# DCDC_5V.net
KiCad netlist of a schematic drawn in Altium Designer
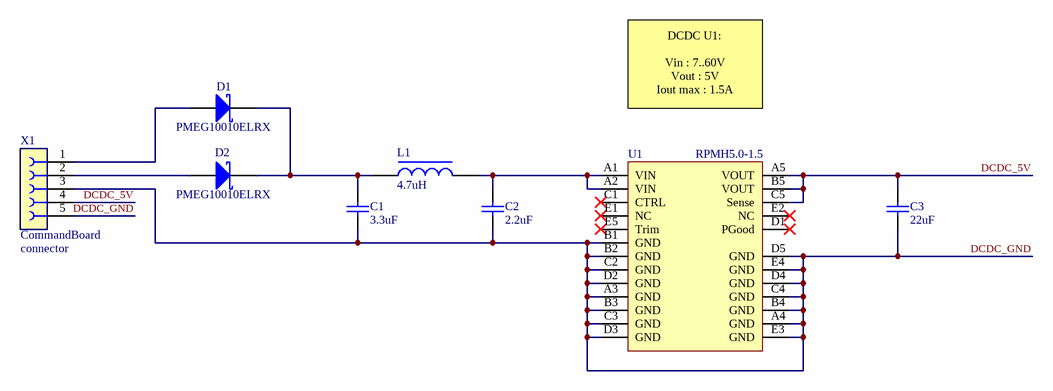
[diagram p0: DCDC_5V.SchDoc]

(export (version "E")
  (design (tool "Eeschema 10.0.6"))
  (components
    (comp (ref "C1")
      (value "3.3uF")
      (footprint "DCDC_5V:CAPC3216X19N")
      (description "3,3µF ±10% 100V Condensateurs céramique X7S 1206 (3216 métrique)")
      (fields (field (name "Comment") "CAP CER 3.3uF 1206"))
      (libsource (lib "DCDC_5V") (part "CAP CER 3.3uF 10% 100V 1206"))
    )
    (comp (ref "C2")
      (value "2.2uF")
      (footprint "DCDC_5V:CAPC3216X19N")
      (description "2,2µF ±10% 75V Condensateurs céramique X7R 1206 (3216 métrique)")
      (fields (field (name "Comment") "CAP CER 2.2uF 1206"))
      (libsource (lib "DCDC_5V") (part "CAP CER 2.2uF 10% 75V 1206"))
    )
    (comp (ref "C3")
      (value "22uF")
      (footprint "DCDC_5V:CAPC1608X08N")
      (description "22µF ±20% 6,3V Condensateurs céramique X5R 0603 (1608 métrique)")
      (fields (field (name "Comment") "CAP CER 22uF 0603"))
      (libsource (lib "DCDC_5V") (part "CAP CER 22uF 200% 6V3 0603"))
    )
    (comp (ref "D1")
      (value "PMEG10010ELRX")
      (footprint "DCDC_5V:DIOM2617X11N")
      (description "Diode Schottky 100V 1A Montage en surface CFP3")
      (fields (field (name "Comment") "DIODE SCHOTTKY 100V 1A SOD123"))
      (libsource (lib "DCDC_5V") (part "DIODE SCHOTTKY 100V 1A SOD123"))
    )
    (comp (ref "D2")
      (value "PMEG10010ELRX")
      (footprint "DCDC_5V:DIOM2617X11N")
      (description "Diode Schottky 100V 1A Montage en surface CFP3")
      (fields (field (name "Comment") "DIODE SCHOTTKY 100V 1A SOD123"))
      (libsource (lib "DCDC_5V") (part "DIODE SCHOTTKY 100V 1A SOD123"))
    )
    (comp (ref "L1")
      (value "4.7uH")
      (footprint "DCDC_5V:INDC2520X12N")
      (description "4,7µH Blindé Inducteur 1,5A 190mOhms maxi 1008 (2520 métrique)")
      (fields (field (name "Comment") "IND SMD 2020"))
      (libsource (lib "DCDC_5V") (part "IND SMD 4.7uH"))
    )
    (comp (ref "U1")
      (value "RPMH5.0-1.5")
      (footprint "DCDC_5V:CONV_RPMH5.0-1.5")
      (fields (field (name "Comment") "DCDC 5V 1.5A"))
      (libsource (lib "DCDC_5V") (part "RPMH5.0-1.5"))
    )
    (comp (ref "X1")
      (value "CONNECT HEADER 5pos 180°")
      (footprint "DCDC_5V:62000611821 - 5pin")
      (fields (field (name "USE") "CommandBoard") (field (name "SYSTEM") "connector"))
      (libsource (lib "DCDC_5V") (part "CONNECT HEADER 5pos 180° 2mm"))
    )
  )
  (nets
    (net (code "1") (name "/DCDC_5V") (class "Default")
      (node (ref "C3") (pin "2") (pinfunction "2_2") (pintype "passive"))
      (node (ref "U1") (pin "A5") (pinfunction "VOUT_A5") (pintype "power_in"))
      (node (ref "U1") (pin "B5") (pinfunction "VOUT_B5") (pintype "power_in"))
      (node (ref "U1") (pin "C5") (pinfunction "Sense_C5") (pintype "power_in"))
      (node (ref "X1") (pin "4") (pinfunction "4_4") (pintype "passive"))
    )
    (net (code "2") (name "/DCDC_GND") (class "Default")
      (node (ref "C1") (pin "1") (pinfunction "1_1") (pintype "passive"))
      (node (ref "C2") (pin "1") (pinfunction "1_1") (pintype "passive"))
      (node (ref "C3") (pin "1") (pinfunction "1_1") (pintype "passive"))
      (node (ref "U1") (pin "A3") (pinfunction "GND_A3") (pintype "power_in"))
      (node (ref "U1") (pin "A4") (pinfunction "GND_A4") (pintype "power_in"))
      (node (ref "U1") (pin "B1") (pinfunction "GND_B1") (pintype "power_in"))
      (node (ref "U1") (pin "B2") (pinfunction "GND_B2") (pintype "power_in"))
      (node (ref "U1") (pin "B3") (pinfunction "GND_B3") (pintype "power_in"))
      (node (ref "U1") (pin "B4") (pinfunction "GND_B4") (pintype "power_in"))
      (node (ref "U1") (pin "C2") (pinfunction "GND_C2") (pintype "power_in"))
      (node (ref "U1") (pin "C3") (pinfunction "GND_C3") (pintype "power_in"))
      (node (ref "U1") (pin "C4") (pinfunction "GND_C4") (pintype "power_in"))
      (node (ref "U1") (pin "D2") (pinfunction "GND_D2") (pintype "power_in"))
      (node (ref "U1") (pin "D3") (pinfunction "GND_D3") (pintype "power_in"))
      (node (ref "U1") (pin "D4") (pinfunction "GND_D4") (pintype "power_in"))
      (node (ref "U1") (pin "D5") (pinfunction "GND_D5") (pintype "power_in"))
      (node (ref "U1") (pin "E3") (pinfunction "GND_E3") (pintype "power_in"))
      (node (ref "U1") (pin "E4") (pinfunction "GND_E4") (pintype "power_in"))
      (node (ref "X1") (pin "3") (pinfunction "3_3") (pintype "passive"))
      (node (ref "X1") (pin "5") (pinfunction "5_5") (pintype "passive"))
    )
    (net (code "3") (name "Net-(C2-Pad2)") (class "Default")
      (node (ref "C2") (pin "2") (pinfunction "2_2") (pintype "passive"))
      (node (ref "L1") (pin "2") (pinfunction "2_2") (pintype "passive"))
      (node (ref "U1") (pin "A1") (pinfunction "VIN_A1") (pintype "power_in"))
      (node (ref "U1") (pin "A2") (pinfunction "VIN_A2") (pintype "power_in"))
    )
    (net (code "4") (name "Net-(D1-A)") (class "Default")
      (node (ref "D1") (pin "2") (pinfunction "A_2") (pintype "passive"))
      (node (ref "X1") (pin "1") (pinfunction "1_1") (pintype "passive"))
    )
    (net (code "5") (name "Net-(D1-K)") (class "Default")
      (node (ref "C1") (pin "2") (pinfunction "2_2") (pintype "passive"))
      (node (ref "D1") (pin "1") (pinfunction "K_1") (pintype "passive"))
      (node (ref "D2") (pin "1") (pinfunction "K_1") (pintype "passive"))
      (node (ref "L1") (pin "1") (pinfunction "1_1") (pintype "passive"))
    )
    (net (code "6") (name "Net-(D2-A)") (class "Default")
      (node (ref "D2") (pin "2") (pinfunction "A_2") (pintype "passive"))
      (node (ref "X1") (pin "2") (pinfunction "2_2") (pintype "passive"))
    )
    (net (code "7") (name "unconnected-(U1-CTRL-PadC1)") (class "Default")
      (node (ref "U1") (pin "C1") (pinfunction "CTRL_C1") (pintype "power_in+no_connect"))
    )
    (net (code "8") (name "unconnected-(U1-NC-PadE1)") (class "Default")
      (node (ref "U1") (pin "E1") (pinfunction "NC_E1") (pintype "power_in+no_connect"))
    )
    (net (code "9") (name "unconnected-(U1-NC-PadE2)") (class "Default")
      (node (ref "U1") (pin "E2") (pinfunction "NC_E2") (pintype "power_in+no_connect"))
    )
    (net (code "10") (name "unconnected-(U1-PGood-PadD1)") (class "Default")
      (node (ref "U1") (pin "D1") (pinfunction "PGood_D1") (pintype "power_in+no_connect"))
    )
    (net (code "11") (name "unconnected-(U1-Trim-PadE5)") (class "Default")
      (node (ref "U1") (pin "E5") (pinfunction "Trim_E5") (pintype "power_in+no_connect"))
    )
  )
)
